# Adafruit_ADS1115_16Bit_I2C_ADC.net
KiCad netlist of a schematic drawn in EAGLE
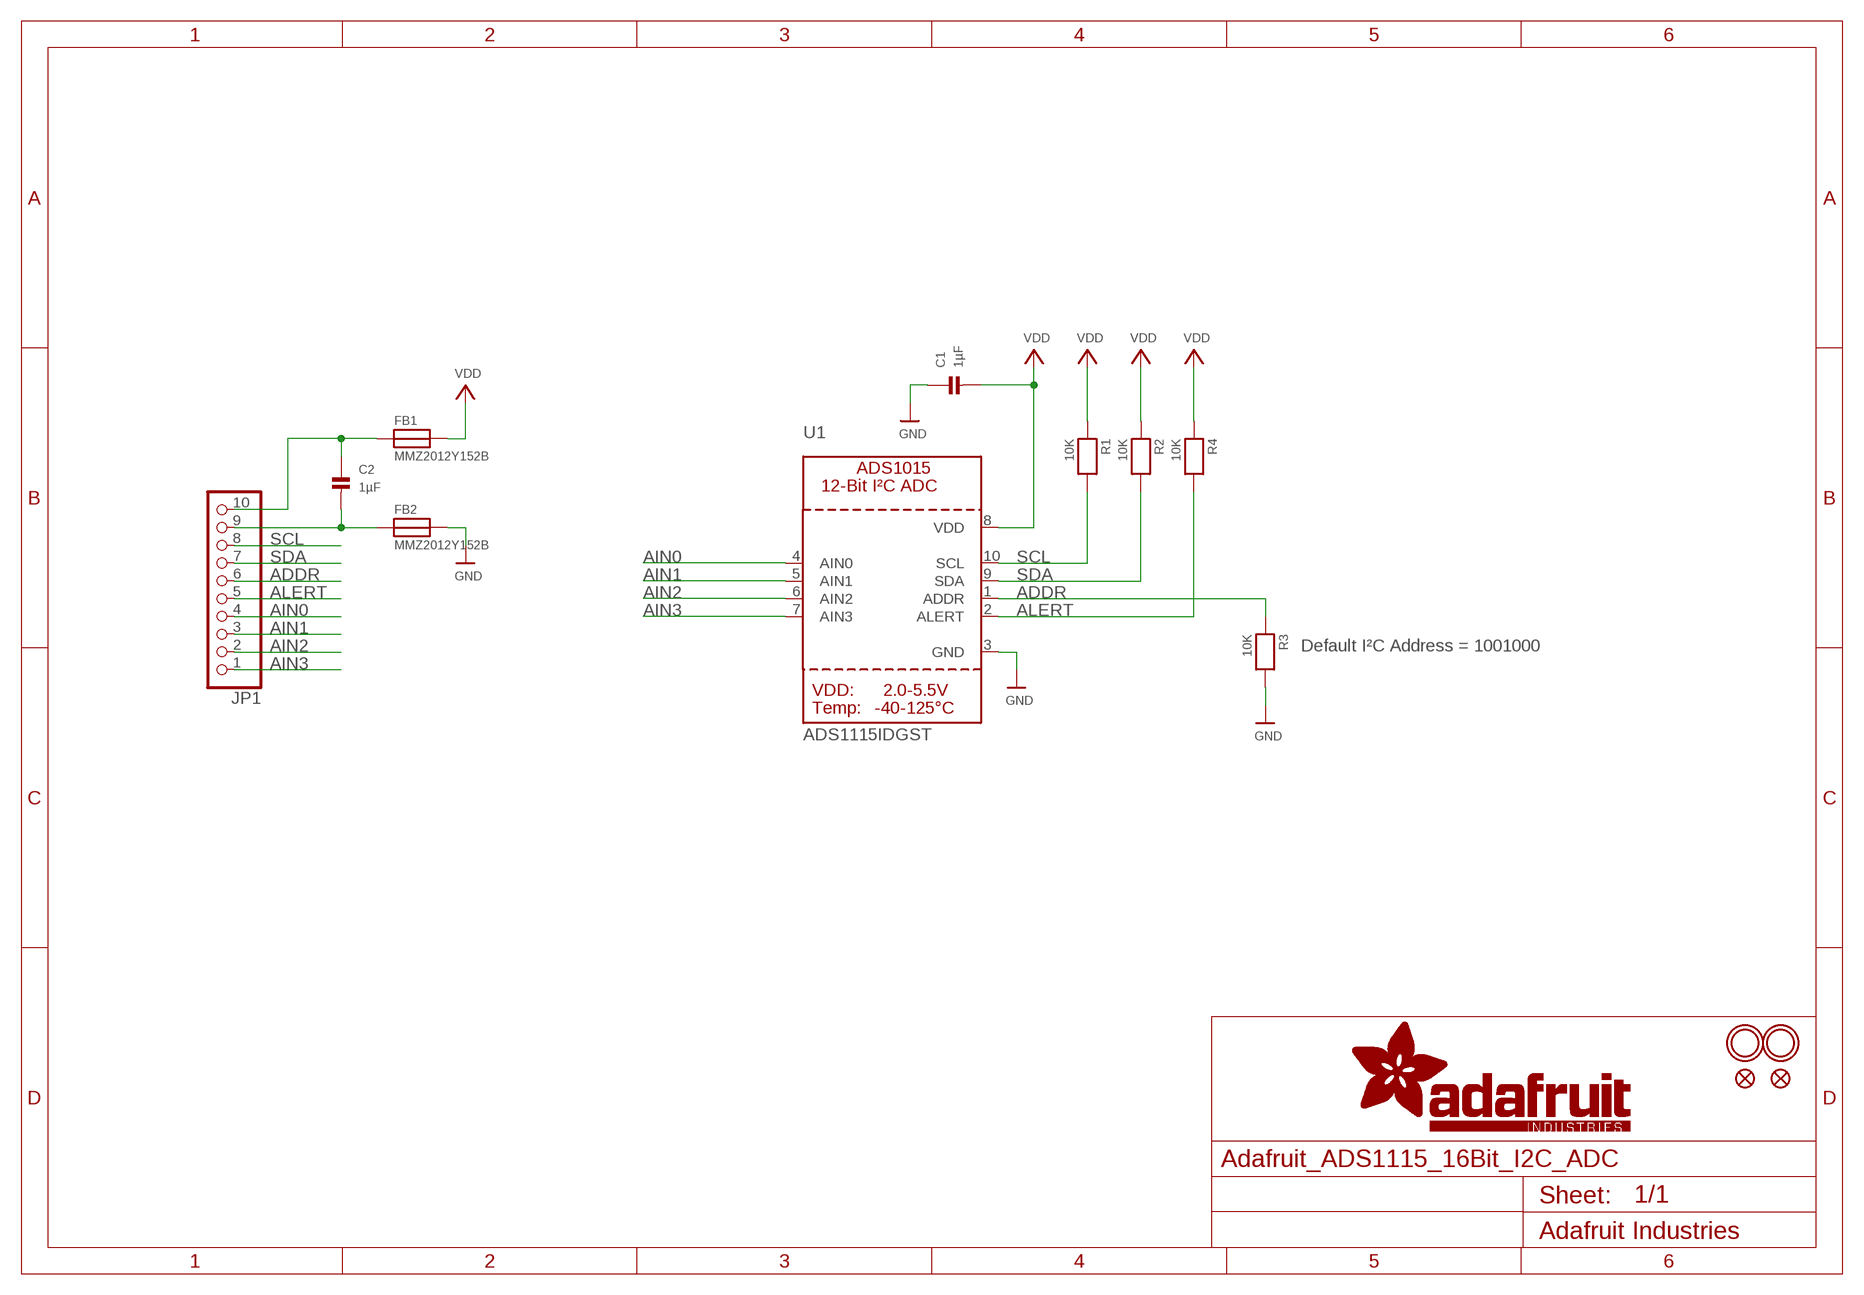
[diagram p0: schematic, sheet 1]

(export (version "E")
  (design (tool "Eeschema 10.0.6"))
  (components
    (comp (ref "C1")
      (value "1µF")
      (footprint "eagle-import:0805")
      (libsource (lib "eagle-import") (part "CAP_CERAMIC0805"))
    )
    (comp (ref "C2")
      (value "1µF")
      (footprint "eagle-import:0805")
      (libsource (lib "eagle-import") (part "CAP_CERAMIC0805"))
    )
    (comp (ref "FB1")
      (value "MMZ2012Y152B")
      (footprint "eagle-import:0805")
      (libsource (lib "eagle-import") (part "FERRITE0805"))
    )
    (comp (ref "FB2")
      (value "MMZ2012Y152B")
      (footprint "eagle-import:0805")
      (libsource (lib "eagle-import") (part "FERRITE0805"))
    )
    (comp (ref "FID1")
      (value "FIDUCIAL\"\"")
      (footprint "eagle-import:FIDUCIAL_1MM")
      (libsource (lib "eagle-import") (part "FIDUCIAL{dblquote}{dblquote}"))
    )
    (comp (ref "FID2")
      (value "FIDUCIAL\"\"")
      (footprint "eagle-import:FIDUCIAL_1MM")
      (libsource (lib "eagle-import") (part "FIDUCIAL{dblquote}{dblquote}"))
    )
    (comp (ref "JP1")
      (value "HEADER-1X1070MIL")
      (footprint "eagle-import:1X10_ROUND70")
      (libsource (lib "eagle-import") (part "HEADER-1X1070MIL"))
    )
    (comp (ref "R1")
      (value "10K")
      (footprint "eagle-import:0805")
      (libsource (lib "eagle-import") (part "RESISTOR0805"))
    )
    (comp (ref "R2")
      (value "10K")
      (footprint "eagle-import:0805")
      (libsource (lib "eagle-import") (part "RESISTOR0805"))
    )
    (comp (ref "R3")
      (value "10K")
      (footprint "eagle-import:0805")
      (libsource (lib "eagle-import") (part "RESISTOR0805"))
    )
    (comp (ref "R4")
      (value "10K")
      (footprint "eagle-import:0805")
      (libsource (lib "eagle-import") (part "RESISTOR0805"))
    )
    (comp (ref "U$13")
      (value "MOUNTINGHOLE2.5")
      (footprint "eagle-import:MOUNTINGHOLE_2.5_PLATED")
      (libsource (lib "eagle-import") (part "MOUNTINGHOLE2.5"))
    )
    (comp (ref "U$14")
      (value "MOUNTINGHOLE2.5")
      (footprint "eagle-import:MOUNTINGHOLE_2.5_PLATED")
      (libsource (lib "eagle-import") (part "MOUNTINGHOLE2.5"))
    )
    (comp (ref "U1")
      (value "ADS1115IDGST")
      (footprint "eagle-import:MSOP10")
      (libsource (lib "eagle-import") (part "ADC_ADS1015"))
    )
  )
  (nets
    (net (code "1") (name "/ADDR") (class "Default")
      (node (ref "JP1") (pin "6") (pinfunction "6_6") (pintype "passive"))
      (node (ref "R3") (pin "1") (pinfunction "1_1") (pintype "passive"))
      (node (ref "U1") (pin "1") (pinfunction "ADDR_1") (pintype "bidirectional"))
    )
    (net (code "2") (name "/AIN0") (class "Default")
      (node (ref "JP1") (pin "4") (pinfunction "4_4") (pintype "passive"))
      (node (ref "U1") (pin "4") (pinfunction "AIN0_4") (pintype "bidirectional"))
    )
    (net (code "3") (name "/AIN1") (class "Default")
      (node (ref "JP1") (pin "3") (pinfunction "3_3") (pintype "passive"))
      (node (ref "U1") (pin "5") (pinfunction "AIN1_5") (pintype "bidirectional"))
    )
    (net (code "4") (name "/AIN2") (class "Default")
      (node (ref "JP1") (pin "2") (pinfunction "2_2") (pintype "passive"))
      (node (ref "U1") (pin "6") (pinfunction "AIN2_6") (pintype "bidirectional"))
    )
    (net (code "5") (name "/AIN3") (class "Default")
      (node (ref "JP1") (pin "1") (pinfunction "1_1") (pintype "passive"))
      (node (ref "U1") (pin "7") (pinfunction "AIN3_7") (pintype "bidirectional"))
    )
    (net (code "6") (name "/ALERT") (class "Default")
      (node (ref "JP1") (pin "5") (pinfunction "5_5") (pintype "passive"))
      (node (ref "R4") (pin "2") (pinfunction "2_2") (pintype "passive"))
      (node (ref "U1") (pin "2") (pinfunction "ALERT_2") (pintype "bidirectional"))
    )
    (net (code "7") (name "/SCL") (class "Default")
      (node (ref "JP1") (pin "8") (pinfunction "8_8") (pintype "passive"))
      (node (ref "R1") (pin "2") (pinfunction "2_2") (pintype "passive"))
      (node (ref "U1") (pin "10") (pinfunction "SCL_10") (pintype "bidirectional"))
    )
    (net (code "8") (name "/SDA") (class "Default")
      (node (ref "JP1") (pin "7") (pinfunction "7_7") (pintype "passive"))
      (node (ref "R2") (pin "2") (pinfunction "2_2") (pintype "passive"))
      (node (ref "U1") (pin "9") (pinfunction "SDA_9") (pintype "bidirectional"))
    )
    (net (code "9") (name "GND") (class "Default")
      (node (ref "C1") (pin "1") (pinfunction "P$1_1") (pintype "passive"))
      (node (ref "FB2") (pin "2") (pinfunction "P$2_2") (pintype "bidirectional"))
      (node (ref "R3") (pin "2") (pinfunction "2_2") (pintype "passive"))
      (node (ref "U1") (pin "3") (pinfunction "GND_3") (pintype "bidirectional"))
    )
    (net (code "10") (name "Net-(C2-P$1)") (class "Default")
      (node (ref "C2") (pin "1") (pinfunction "P$1_1") (pintype "passive"))
      (node (ref "FB1") (pin "1") (pinfunction "P$1_1") (pintype "bidirectional"))
      (node (ref "JP1") (pin "10") (pinfunction "10_10") (pintype "passive"))
    )
    (net (code "11") (name "Net-(C2-P$2)") (class "Default")
      (node (ref "C2") (pin "2") (pinfunction "P$2_2") (pintype "passive"))
      (node (ref "FB2") (pin "1") (pinfunction "P$1_1") (pintype "bidirectional"))
      (node (ref "JP1") (pin "9") (pinfunction "9_9") (pintype "passive"))
    )
    (net (code "12") (name "VDD") (class "Default")
      (node (ref "C1") (pin "2") (pinfunction "P$2_2") (pintype "passive"))
      (node (ref "FB1") (pin "2") (pinfunction "P$2_2") (pintype "bidirectional"))
      (node (ref "R1") (pin "1") (pinfunction "1_1") (pintype "passive"))
      (node (ref "R2") (pin "1") (pinfunction "1_1") (pintype "passive"))
      (node (ref "R4") (pin "1") (pinfunction "1_1") (pintype "passive"))
      (node (ref "U1") (pin "8") (pinfunction "VDD_8") (pintype "bidirectional"))
    )
  )
)
